# fuse-b-1.net
KiCad netlist of a schematic drawn in EAGLE
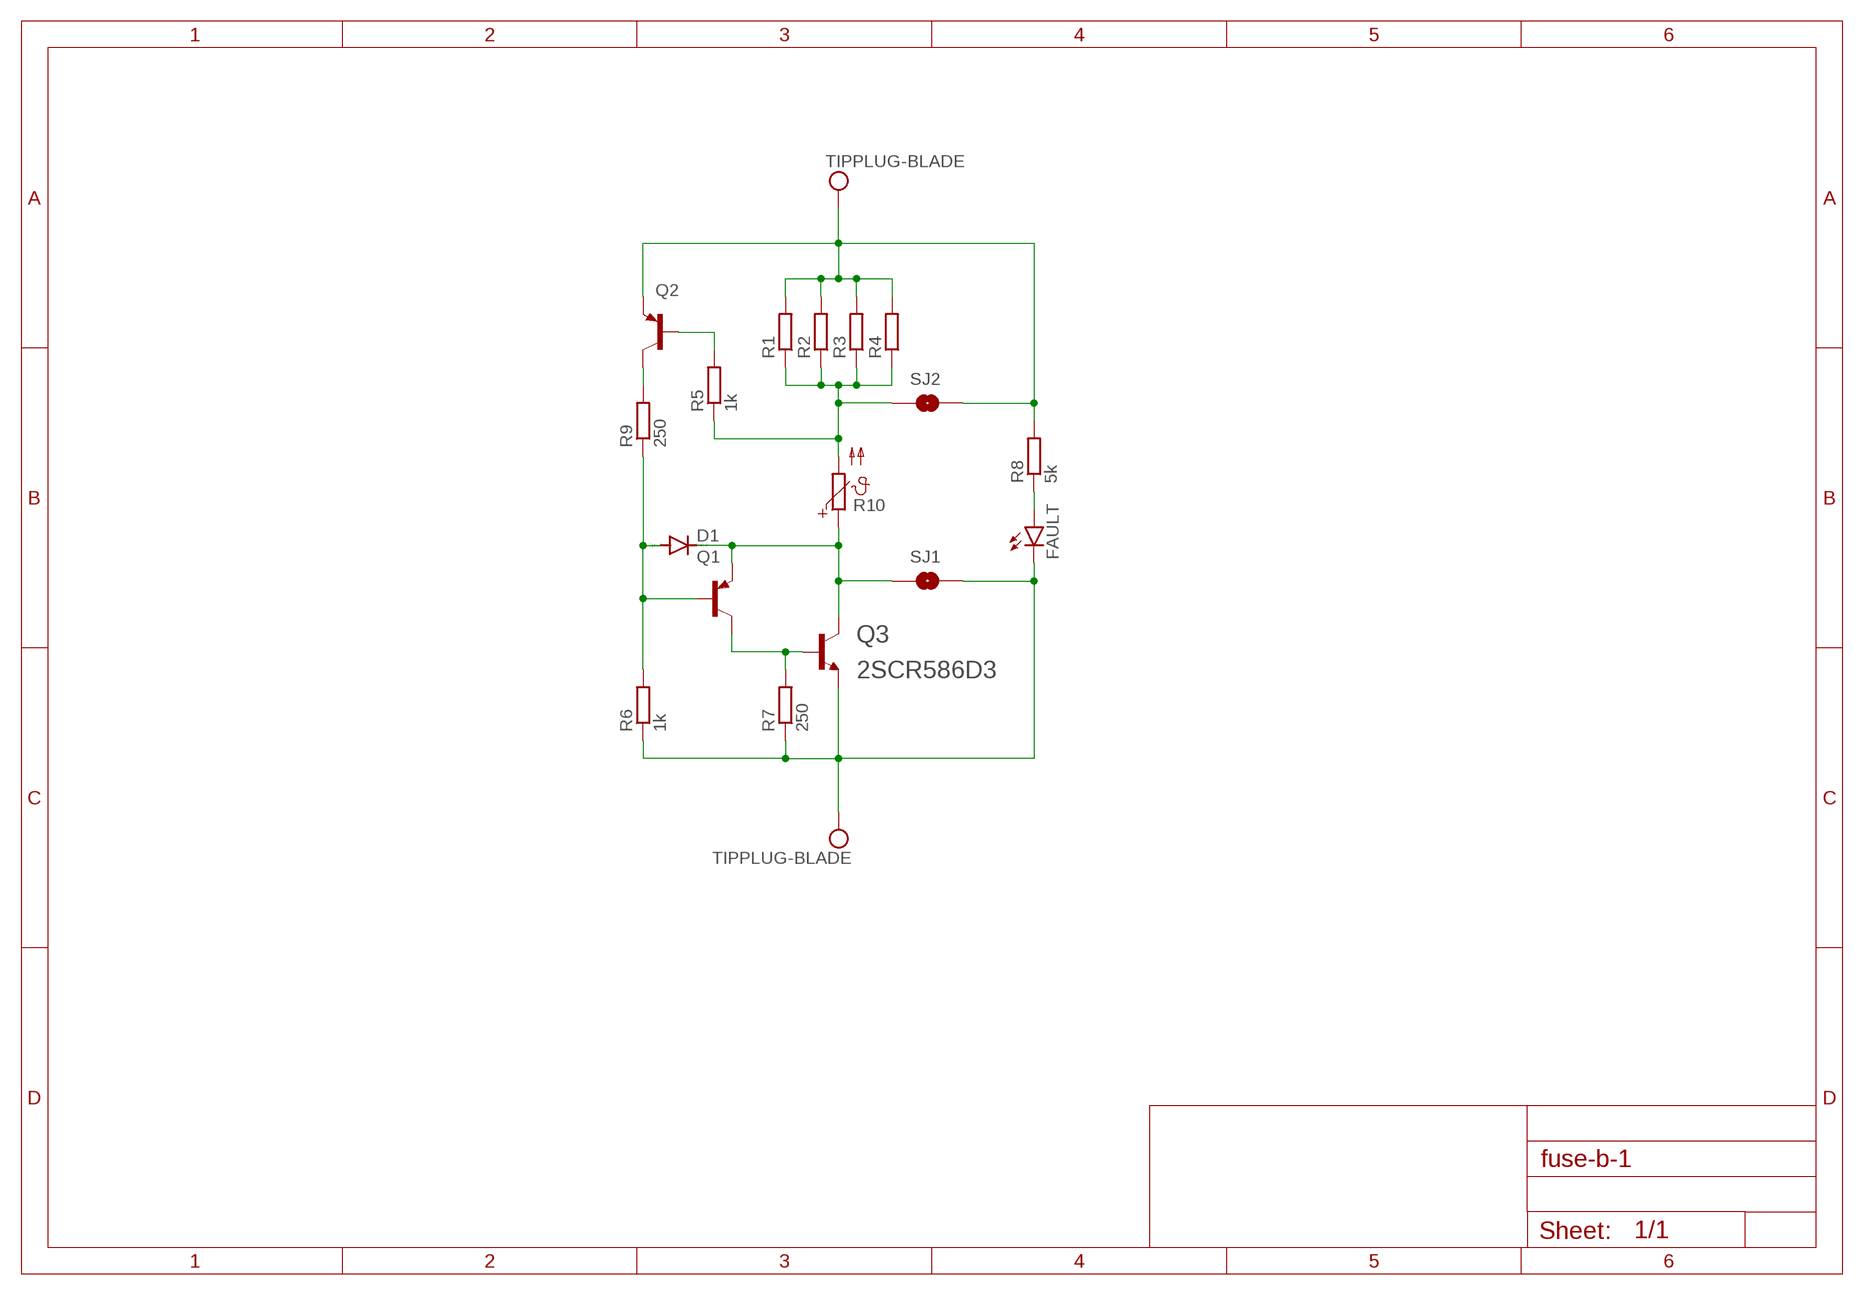
[diagram p0: schematic, sheet 1]

(export (version "E")
  (design (tool "Eeschema 10.0.6"))
  (components
    (comp (ref "D1")
      (value "DIODE-MINIMELF")
      (footprint "eagle-import:MINIMELF")
      (libsource (lib "eagle-import") (part "DIODE-MINIMELF"))
    )
    (comp (ref "FAULT")
      (value "LEDCHIPLED_0603")
      (footprint "eagle-import:CHIPLED_0603")
      (libsource (lib "eagle-import") (part "LEDCHIPLED_0603"))
    )
    (comp (ref "Q1")
      (value "BCX71SMD")
      (footprint "eagle-import:SOT23")
      (libsource (lib "eagle-import") (part "BCX71SMD"))
    )
    (comp (ref "Q2")
      (value "BCX71SMD")
      (footprint "eagle-import:SOT23")
      (libsource (lib "eagle-import") (part "BCX71SMD"))
    )
    (comp (ref "Q3")
      (value "2SCR586D3")
      (footprint "eagle-import:D-PAK_TO252AA")
      (libsource (lib "eagle-import") (part "2SCR586D3TL1"))
    )
    (comp (ref "R1")
      (value "R-EU_R2512")
      (footprint "eagle-import:R2512")
      (libsource (lib "eagle-import") (part "R-EU_R2512"))
    )
    (comp (ref "R2")
      (value "R-EU_R2512")
      (footprint "eagle-import:R2512")
      (libsource (lib "eagle-import") (part "R-EU_R2512"))
    )
    (comp (ref "R3")
      (value "R-EU_R2512")
      (footprint "eagle-import:R2512")
      (libsource (lib "eagle-import") (part "R-EU_R2512"))
    )
    (comp (ref "R4")
      (value "R-EU_R2512")
      (footprint "eagle-import:R2512")
      (libsource (lib "eagle-import") (part "R-EU_R2512"))
    )
    (comp (ref "R5")
      (value "1k")
      (footprint "eagle-import:R0805")
      (libsource (lib "eagle-import") (part "R-EU_R0805"))
    )
    (comp (ref "R6")
      (value "1k")
      (footprint "eagle-import:R0805")
      (libsource (lib "eagle-import") (part "R-EU_R0805"))
    )
    (comp (ref "R7")
      (value "250")
      (footprint "eagle-import:R0805")
      (libsource (lib "eagle-import") (part "R-EU_R0805"))
    )
    (comp (ref "R8")
      (value "5k")
      (footprint "eagle-import:R0805")
      (libsource (lib "eagle-import") (part "R-EU_R0805"))
    )
    (comp (ref "R9")
      (value "250")
      (footprint "eagle-import:R0805")
      (libsource (lib "eagle-import") (part "R-EU_R0805"))
    )
    (comp (ref "R10")
      (value "PTC_1812")
      (footprint "eagle-import:PTC1812")
      (libsource (lib "eagle-import") (part "PTC_1812"))
    )
    (comp (ref "SJ1")
      (value "SJRND2")
      (footprint "eagle-import:SJ_RND2")
      (libsource (lib "eagle-import") (part "SJRND2"))
    )
    (comp (ref "SJ2")
      (value "SJRND2")
      (footprint "eagle-import:SJ_RND2")
      (libsource (lib "eagle-import") (part "SJRND2"))
    )
    (comp (ref "U$1")
      (value "TIPPLUG-BLADE")
      (footprint "eagle-import:BLADEPLUG-9.5X1.25")
      (libsource (lib "eagle-import") (part "TIPPLUG-BLADE"))
    )
    (comp (ref "U$2")
      (value "TIPPLUG-BLADE")
      (footprint "eagle-import:BLADEPLUG-9.5X1.25")
      (libsource (lib "eagle-import") (part "TIPPLUG-BLADE"))
    )
  )
  (nets
    (net (code "1") (name "Net-(FAULT-PadA)") (class "Default")
      (node (ref "FAULT") (pin "A") (pinfunction "A_A") (pintype "passive"))
      (node (ref "R8") (pin "1") (pinfunction "1_1") (pintype "passive"))
    )
    (net (code "2") (name "Net-(Q1-B)") (class "Default")
      (node (ref "D1") (pin "A") (pinfunction "A_A") (pintype "passive"))
      (node (ref "Q1") (pin "1") (pinfunction "B_1") (pintype "passive"))
      (node (ref "R6") (pin "2") (pinfunction "2_2") (pintype "passive"))
      (node (ref "R9") (pin "1") (pinfunction "1_1") (pintype "passive"))
    )
    (net (code "3") (name "Net-(Q1-C)") (class "Default")
      (node (ref "Q1") (pin "3") (pinfunction "C_3") (pintype "passive"))
      (node (ref "Q3") (pin "1") (pinfunction "B_1") (pintype "passive"))
      (node (ref "R7") (pin "2") (pinfunction "2_2") (pintype "passive"))
    )
    (net (code "4") (name "Net-(Q1-E)") (class "Default")
      (node (ref "D1") (pin "C") (pinfunction "C_C") (pintype "passive"))
      (node (ref "Q1") (pin "2") (pinfunction "E_2") (pintype "passive"))
      (node (ref "Q3") (pin "4") (pinfunction "C_4") (pintype "passive"))
      (node (ref "R10") (pin "1") (pinfunction "1_1") (pintype "passive"))
      (node (ref "SJ1") (pin "P$1") (pinfunction "1_P$1") (pintype "passive"))
    )
    (net (code "5") (name "Net-(Q2-B)") (class "Default")
      (node (ref "Q2") (pin "1") (pinfunction "B_1") (pintype "passive"))
      (node (ref "R5") (pin "2") (pinfunction "2_2") (pintype "passive"))
    )
    (net (code "6") (name "Net-(Q2-C)") (class "Default")
      (node (ref "Q2") (pin "3") (pinfunction "C_3") (pintype "passive"))
      (node (ref "R9") (pin "2") (pinfunction "2_2") (pintype "passive"))
    )
    (net (code "7") (name "Net-(Q2-E)") (class "Default")
      (node (ref "Q2") (pin "2") (pinfunction "E_2") (pintype "passive"))
      (node (ref "R1") (pin "2") (pinfunction "2_2") (pintype "passive"))
      (node (ref "R2") (pin "2") (pinfunction "2_2") (pintype "passive"))
      (node (ref "R3") (pin "2") (pinfunction "2_2") (pintype "passive"))
      (node (ref "R4") (pin "2") (pinfunction "2_2") (pintype "passive"))
      (node (ref "R8") (pin "2") (pinfunction "2_2") (pintype "passive"))
      (node (ref "SJ2") (pin "P$2") (pinfunction "2_P$2") (pintype "passive"))
      (node (ref "U$1") (pin "PB") (pinfunction "$1_PB") (pintype "passive"))
      (node (ref "U$1") (pin "PT") (pinfunction "$1_PT") (pintype "passive"))
    )
    (net (code "8") (name "Net-(Q3-E)") (class "Default")
      (node (ref "FAULT") (pin "C") (pinfunction "C_C") (pintype "passive"))
      (node (ref "Q3") (pin "3") (pinfunction "E_3") (pintype "passive"))
      (node (ref "R6") (pin "1") (pinfunction "1_1") (pintype "passive"))
      (node (ref "R7") (pin "1") (pinfunction "1_1") (pintype "passive"))
      (node (ref "SJ1") (pin "P$2") (pinfunction "2_P$2") (pintype "passive"))
      (node (ref "U$2") (pin "PB") (pinfunction "$1_PB") (pintype "passive"))
      (node (ref "U$2") (pin "PT") (pinfunction "$1_PT") (pintype "passive"))
    )
    (net (code "9") (name "Net-(SJ2-1)") (class "Default")
      (node (ref "R1") (pin "1") (pinfunction "1_1") (pintype "passive"))
      (node (ref "R10") (pin "2") (pinfunction "2_2") (pintype "passive"))
      (node (ref "R2") (pin "1") (pinfunction "1_1") (pintype "passive"))
      (node (ref "R3") (pin "1") (pinfunction "1_1") (pintype "passive"))
      (node (ref "R4") (pin "1") (pinfunction "1_1") (pintype "passive"))
      (node (ref "R5") (pin "1") (pinfunction "1_1") (pintype "passive"))
      (node (ref "SJ2") (pin "P$1") (pinfunction "1_P$1") (pintype "passive"))
    )
  )
)
